# LVDS_eDP.net
KiCad netlist of a schematic drawn in Altium Designer
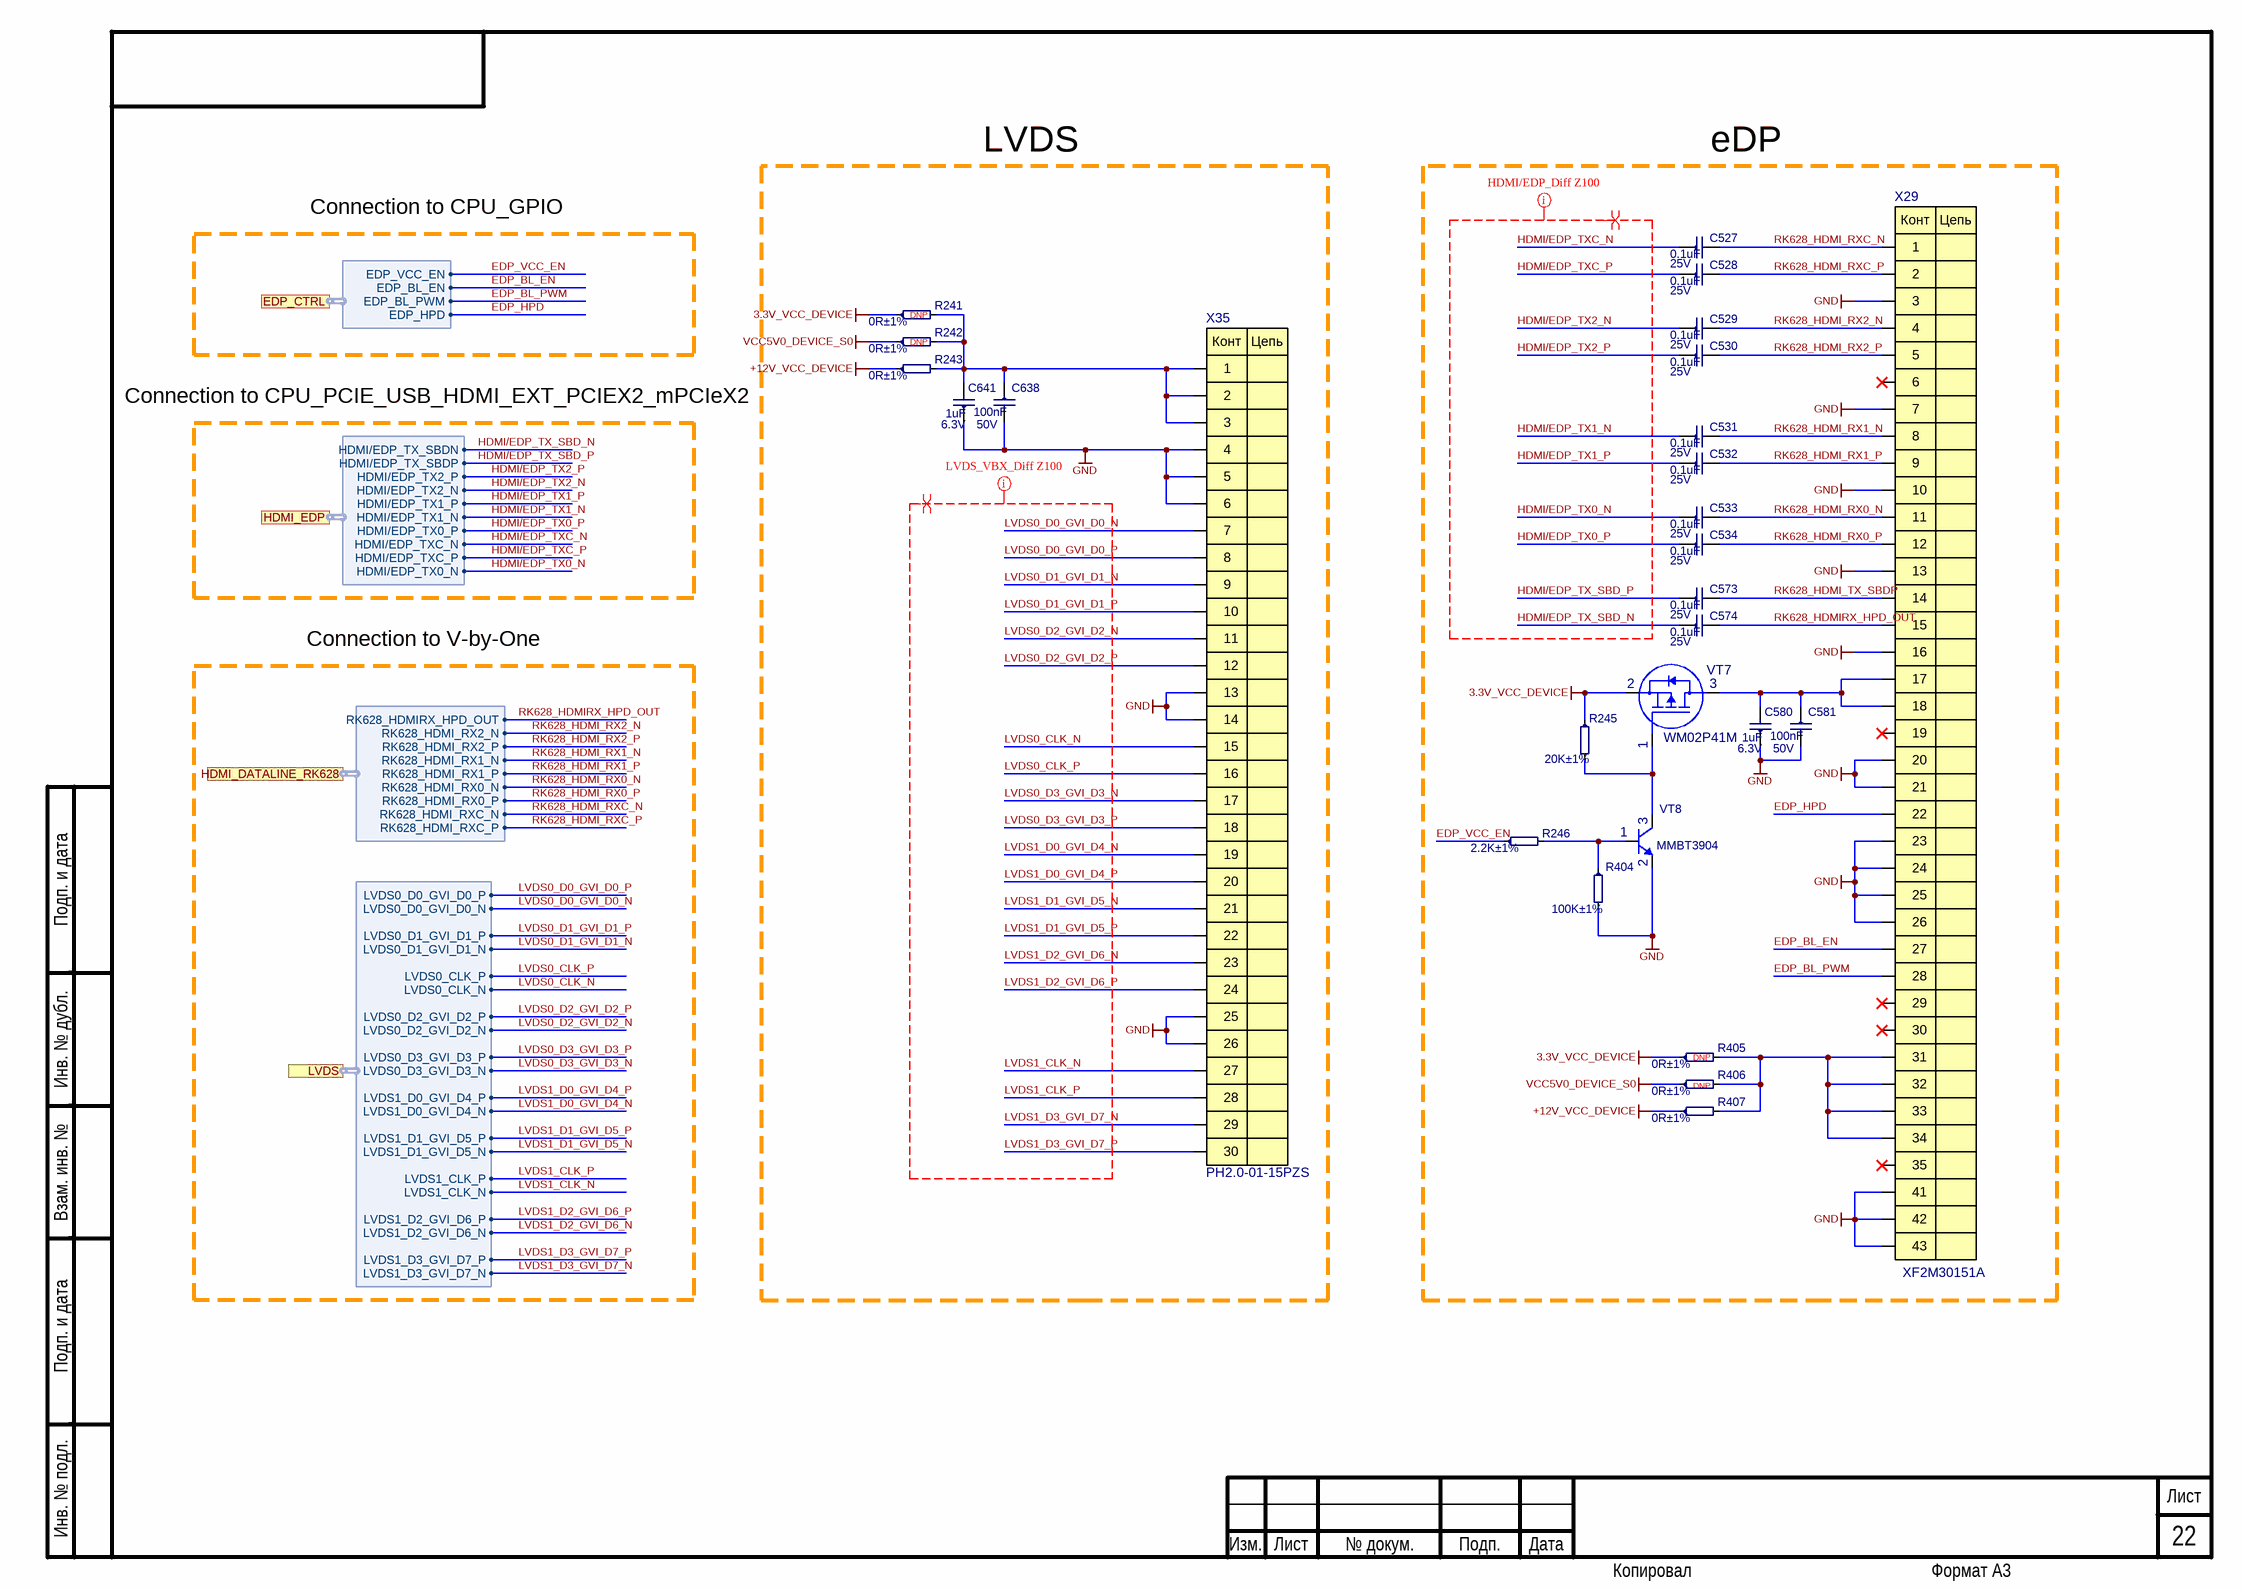
[diagram p0: LVDS_eDP.SchDoc]

(export (version "E")
  (design (tool "Eeschema 10.0.6"))
  (components
    (comp (ref "C527")
      (value "0.1uF")
      (footprint "C0201")
      (fields
        (field (name "VOLTAGE") "25V")
        (field (name "PART NUMBER") "0201-X5R-25V-0.1uF±10%")
        (field (name "TOLERANCE") "10%")
        (field (name "MANUFACTURER") "Yageo")
      )
      (libsource (lib "ATB") (part "C"))
    )
    (comp (ref "C528")
      (value "0.1uF")
      (footprint "C0201")
      (fields
        (field (name "VOLTAGE") "25V")
        (field (name "PART NUMBER") "0201-X5R-25V-0.1uF±10%")
        (field (name "TOLERANCE") "10%")
        (field (name "MANUFACTURER") "Yageo")
      )
      (libsource (lib "ATB") (part "C"))
    )
    (comp (ref "C529")
      (value "0.1uF")
      (footprint "C0201")
      (fields
        (field (name "VOLTAGE") "25V")
        (field (name "PART NUMBER") "0201-X5R-25V-0.1uF±10%")
        (field (name "TOLERANCE") "10%")
        (field (name "MANUFACTURER") "Yageo")
      )
      (libsource (lib "ATB") (part "C"))
    )
    (comp (ref "C530")
      (value "0.1uF")
      (footprint "C0201")
      (fields
        (field (name "VOLTAGE") "25V")
        (field (name "PART NUMBER") "0201-X5R-25V-0.1uF±10%")
        (field (name "TOLERANCE") "10%")
        (field (name "MANUFACTURER") "Yageo")
      )
      (libsource (lib "ATB") (part "C"))
    )
    (comp (ref "C531")
      (value "0.1uF")
      (footprint "C0201")
      (fields
        (field (name "VOLTAGE") "25V")
        (field (name "PART NUMBER") "0201-X5R-25V-0.1uF±10%")
        (field (name "TOLERANCE") "10%")
        (field (name "MANUFACTURER") "Yageo")
      )
      (libsource (lib "ATB") (part "C"))
    )
    (comp (ref "C532")
      (value "0.1uF")
      (footprint "C0201")
      (fields
        (field (name "VOLTAGE") "25V")
        (field (name "PART NUMBER") "0201-X5R-25V-0.1uF±10%")
        (field (name "TOLERANCE") "10%")
        (field (name "MANUFACTURER") "Yageo")
      )
      (libsource (lib "ATB") (part "C"))
    )
    (comp (ref "C533")
      (value "0.1uF")
      (footprint "C0201")
      (fields
        (field (name "VOLTAGE") "25V")
        (field (name "PART NUMBER") "0201-X5R-25V-0.1uF±10%")
        (field (name "TOLERANCE") "10%")
        (field (name "MANUFACTURER") "Yageo")
      )
      (libsource (lib "ATB") (part "C"))
    )
    (comp (ref "C534")
      (value "0.1uF")
      (footprint "C0201")
      (fields
        (field (name "VOLTAGE") "25V")
        (field (name "PART NUMBER") "0201-X5R-25V-0.1uF±10%")
        (field (name "TOLERANCE") "10%")
        (field (name "MANUFACTURER") "Yageo")
      )
      (libsource (lib "ATB") (part "C"))
    )
    (comp (ref "C573")
      (value "0.1uF")
      (footprint "C0201")
      (fields
        (field (name "VOLTAGE") "25V")
        (field (name "PART NUMBER") "0201-X5R-25V-0.1uF±10%")
        (field (name "TOLERANCE") "10%")
        (field (name "MANUFACTURER") "Yageo")
      )
      (libsource (lib "ATB") (part "C"))
    )
    (comp (ref "C574")
      (value "0.1uF")
      (footprint "C0201")
      (fields
        (field (name "VOLTAGE") "25V")
        (field (name "PART NUMBER") "0201-X5R-25V-0.1uF±10%")
        (field (name "TOLERANCE") "10%")
        (field (name "MANUFACTURER") "Yageo")
      )
      (libsource (lib "ATB") (part "C"))
    )
    (comp (ref "C580")
      (value "1uF")
      (footprint "C0201")
      (fields
        (field (name "VOLTAGE") "6.3V")
        (field (name "PART NUMBER") "0201-X5R-6.3V-1uF±20%")
        (field (name "TOLERANCE") "20%")
        (field (name "MANUFACTURER") "Murata Electronics")
      )
      (libsource (lib "ATB") (part "C"))
    )
    (comp (ref "C581")
      (value "100nF")
      (footprint "C0402")
      (description "Ceramic Capacitor 0402 100nF ±10% 50V X7R")
      (fields
        (field (name "VOLTAGE") "50V")
        (field (name "PART NUMBER") "0402-X7R-50V-0.1uF±10%")
        (field (name "TOLERANCE") "10%")
      )
      (libsource (lib "ATB") (part "C"))
    )
    (comp (ref "C638")
      (value "100nF")
      (footprint "C0402")
      (description "Ceramic Capacitor 0402 100nF ±10% 50V X7R")
      (fields
        (field (name "VOLTAGE") "50V")
        (field (name "PART NUMBER") "0402-X7R-50V-0.1uF±10%")
        (field (name "TOLERANCE") "10%")
      )
      (libsource (lib "ATB") (part "C"))
    )
    (comp (ref "C641")
      (value "1uF")
      (footprint "C0201")
      (fields
        (field (name "VOLTAGE") "6.3V")
        (field (name "PART NUMBER") "0201-X5R-6.3V-1uF±20%")
        (field (name "TOLERANCE") "20%")
        (field (name "MANUFACTURER") "Murata Electronics")
      )
      (libsource (lib "ATB") (part "C"))
    )
    (comp (ref "R241")
      (value "0R±1%")
      (footprint "R0402")
      (description "Chip Resistor 0402 0Ω ±1% 50V ±100ppm/℃ Thick Film")
      (fields (field (name "PART NUMBER") "0402-0.0625W-0R-100ppm±1%") (field (name "TOLERANCE") "1%"))
      (libsource (lib "ATB") (part "R"))
    )
    (comp (ref "R242")
      (value "0R±1%")
      (footprint "R0402")
      (description "Chip Resistor 0402 0Ω ±1% 50V ±100ppm/℃ Thick Film")
      (fields (field (name "PART NUMBER") "0402-0.0625W-0R-100ppm±1%") (field (name "TOLERANCE") "1%"))
      (libsource (lib "ATB") (part "R"))
    )
    (comp (ref "R243")
      (value "0R±1%")
      (footprint "R0402")
      (description "Chip Resistor 0402 0Ω ±1% 50V ±100ppm/℃ Thick Film")
      (fields (field (name "PART NUMBER") "0402-0.0625W-0R-100ppm±1%") (field (name "TOLERANCE") "1%"))
      (libsource (lib "ATB") (part "R"))
    )
    (comp (ref "R245")
      (value "20K±1%")
      (footprint "R0402")
      (description "Chip Resistor 0402 20kΩ ±1% 50V ±100ppm/℃ Thick Film")
      (fields (field (name "PART NUMBER") "0402-0.0625W-20K-100ppm±1%") (field (name "TOLERANCE") "1%"))
      (libsource (lib "ATB") (part "R"))
    )
    (comp (ref "R246")
      (value "2.2K±1%")
      (footprint "R0402")
      (fields
        (field (name "PART NUMBER") "0402-0.0625W-2.2K-100ppm±1%")
        (field (name "TOLERANCE") "1%")
        (field (name "MANUFACTURER") "Yageo")
      )
      (libsource (lib "ATB") (part "R"))
    )
    (comp (ref "R404")
      (value "100K±1%")
      (footprint "R0402")
      (description "Chip Resistor 0402 100kΩ ±1% 50V ±100ppm/℃ Thick Film")
      (fields (field (name "PART NUMBER") "0402-0.0625W-100K-100ppm±1%") (field (name "TOLERANCE") "1%"))
      (libsource (lib "ATB") (part "R"))
    )
    (comp (ref "R405")
      (value "0R±1%")
      (footprint "R0402")
      (description "Chip Resistor 0402 0Ω ±1% 50V ±100ppm/℃ Thick Film")
      (fields (field (name "PART NUMBER") "0402-0.0625W-0R-100ppm±1%") (field (name "TOLERANCE") "1%"))
      (libsource (lib "ATB") (part "R"))
    )
    (comp (ref "R406")
      (value "0R±1%")
      (footprint "R0402")
      (description "Chip Resistor 0402 0Ω ±1% 50V ±100ppm/℃ Thick Film")
      (fields (field (name "PART NUMBER") "0402-0.0625W-0R-100ppm±1%") (field (name "TOLERANCE") "1%"))
      (libsource (lib "ATB") (part "R"))
    )
    (comp (ref "R407")
      (value "0R±1%")
      (footprint "R0402")
      (description "Chip Resistor 0402 0Ω ±1% 50V ±100ppm/℃ Thick Film")
      (fields (field (name "PART NUMBER") "0402-0.0625W-0R-100ppm±1%") (field (name "TOLERANCE") "1%"))
      (libsource (lib "ATB") (part "R"))
    )
    (comp (ref "VT7")
      (value "WM02P41M")
      (footprint "SOT23")
      (description "Small signal mosfet")
      (fields (field (name "VOLTAGE") "-20V") (field (name "MANUFACTURER") "Wayon"))
      (libsource (lib "ATB") (part "WM02P41M"))
    )
    (comp (ref "VT8")
      (value "MMBT3904")
      (footprint "SOT23")
      (description "NPN transistor")
      (fields (field (name "VOLTAGE") "40V") (field (name "MANUFACTURER") "Diotec Semiconductor"))
      (libsource (lib "ATB") (part "BC846BLT1G"))
    )
    (comp (ref "X29")
      (value "XF2M30151A")
      (footprint "XF2M30151A")
      (description "FFC разъем, 30PIN, 0.5мм, 50В")
      (fields (field (name "MANUFACTURER") "Omron"))
      (libsource (lib "LIB_RK") (part "XF2M30151A"))
    )
    (comp (ref "X35")
      (value "PH2.0-01-15PZS")
      (footprint "PH2.0-01-15PZS")
      (description "Pin Header 30 Position 2mm Pitch Dual Row Through Hole -40℃~+105℃")
      (fields (field (name "MANUFACTURER") "XUNPU"))
      (libsource (lib "LIB_RK") (part "PH2.0-01-15PZS"))
    )
  )
  (nets
    (net (code "5") (name "+12V_VCC_DEVICE") (class "Default")
      (node (ref "R243") (pin "1") (pinfunction "1_1") (pintype "passive"))
      (node (ref "R407") (pin "1") (pinfunction "1_1") (pintype "passive"))
    )
    (net (code "6") (name "/EDP_BL_EN") (class "Default")
      (node (ref "X29") (pin "27") (pinfunction "27_27") (pintype "passive"))
    )
    (net (code "7") (name "/EDP_BL_PWM") (class "Default")
      (node (ref "X29") (pin "28") (pinfunction "28_28") (pintype "passive"))
    )
    (net (code "8") (name "/EDP_HPD") (class "Default")
      (node (ref "X29") (pin "22") (pinfunction "22_22") (pintype "passive"))
    )
    (net (code "9") (name "/EDP_VCC_EN") (class "Default")
      (node (ref "R246") (pin "1") (pinfunction "1_1") (pintype "passive"))
    )
    (net (code "10") (name "/HDMI{slash}EDP_TX0_N") (class "Default")
      (node (ref "C533") (pin "1") (pinfunction "1_1") (pintype "passive"))
    )
    (net (code "11") (name "/HDMI{slash}EDP_TX0_P") (class "Default")
      (node (ref "C534") (pin "1") (pinfunction "1_1") (pintype "passive"))
    )
    (net (code "12") (name "/HDMI{slash}EDP_TX1_N") (class "Default")
      (node (ref "C531") (pin "1") (pinfunction "1_1") (pintype "passive"))
    )
    (net (code "13") (name "/HDMI{slash}EDP_TX1_P") (class "Default")
      (node (ref "C532") (pin "1") (pinfunction "1_1") (pintype "passive"))
    )
    (net (code "14") (name "/HDMI{slash}EDP_TX2_N") (class "Default")
      (node (ref "C529") (pin "1") (pinfunction "1_1") (pintype "passive"))
    )
    (net (code "15") (name "/HDMI{slash}EDP_TX2_P") (class "Default")
      (node (ref "C530") (pin "1") (pinfunction "1_1") (pintype "passive"))
    )
    (net (code "16") (name "/HDMI{slash}EDP_TXC_N") (class "Default")
      (node (ref "C527") (pin "1") (pinfunction "1_1") (pintype "passive"))
    )
    (net (code "17") (name "/HDMI{slash}EDP_TXC_P") (class "Default")
      (node (ref "C528") (pin "1") (pinfunction "1_1") (pintype "passive"))
    )
    (net (code "18") (name "/HDMI{slash}EDP_TX_SBD_N") (class "Default")
      (node (ref "C574") (pin "1") (pinfunction "1_1") (pintype "passive"))
    )
    (net (code "19") (name "/HDMI{slash}EDP_TX_SBD_P") (class "Default")
      (node (ref "C573") (pin "1") (pinfunction "1_1") (pintype "passive"))
    )
    (net (code "20") (name "/LVDS0_CLK_N") (class "Default")
      (node (ref "X35") (pin "15") (pinfunction "15_15") (pintype "passive"))
    )
    (net (code "21") (name "/LVDS0_CLK_P") (class "Default")
      (node (ref "X35") (pin "16") (pinfunction "16_16") (pintype "passive"))
    )
    (net (code "22") (name "/LVDS0_D0_GVI_D0_N") (class "Default")
      (node (ref "X35") (pin "7") (pinfunction "7_7") (pintype "passive"))
    )
    (net (code "23") (name "/LVDS0_D0_GVI_D0_P") (class "Default")
      (node (ref "X35") (pin "8") (pinfunction "8_8") (pintype "passive"))
    )
    (net (code "24") (name "/LVDS0_D1_GVI_D1_N") (class "Default")
      (node (ref "X35") (pin "9") (pinfunction "9_9") (pintype "passive"))
    )
    (net (code "25") (name "/LVDS0_D1_GVI_D1_P") (class "Default")
      (node (ref "X35") (pin "10") (pinfunction "10_10") (pintype "passive"))
    )
    (net (code "26") (name "/LVDS0_D2_GVI_D2_N") (class "Default")
      (node (ref "X35") (pin "11") (pinfunction "11_11") (pintype "passive"))
    )
    (net (code "27") (name "/LVDS0_D2_GVI_D2_P") (class "Default")
      (node (ref "X35") (pin "12") (pinfunction "12_12") (pintype "passive"))
    )
    (net (code "28") (name "/LVDS0_D3_GVI_D3_N") (class "Default")
      (node (ref "X35") (pin "17") (pinfunction "17_17") (pintype "passive"))
    )
    (net (code "29") (name "/LVDS0_D3_GVI_D3_P") (class "Default")
      (node (ref "X35") (pin "18") (pinfunction "18_18") (pintype "passive"))
    )
    (net (code "30") (name "/LVDS1_CLK_N") (class "Default")
      (node (ref "X35") (pin "27") (pinfunction "27_27") (pintype "passive"))
    )
    (net (code "31") (name "/LVDS1_CLK_P") (class "Default")
      (node (ref "X35") (pin "28") (pinfunction "28_28") (pintype "passive"))
    )
    (net (code "32") (name "/LVDS1_D0_GVI_D4_N") (class "Default")
      (node (ref "X35") (pin "19") (pinfunction "19_19") (pintype "passive"))
    )
    (net (code "33") (name "/LVDS1_D0_GVI_D4_P") (class "Default")
      (node (ref "X35") (pin "20") (pinfunction "20_20") (pintype "passive"))
    )
    (net (code "34") (name "/LVDS1_D1_GVI_D5_N") (class "Default")
      (node (ref "X35") (pin "21") (pinfunction "21_21") (pintype "passive"))
    )
    (net (code "35") (name "/LVDS1_D1_GVI_D5_P") (class "Default")
      (node (ref "X35") (pin "22") (pinfunction "22_22") (pintype "passive"))
    )
    (net (code "36") (name "/LVDS1_D2_GVI_D6_N") (class "Default")
      (node (ref "X35") (pin "23") (pinfunction "23_23") (pintype "passive"))
    )
    (net (code "37") (name "/LVDS1_D2_GVI_D6_P") (class "Default")
      (node (ref "X35") (pin "24") (pinfunction "24_24") (pintype "passive"))
    )
    (net (code "38") (name "/LVDS1_D3_GVI_D7_N") (class "Default")
      (node (ref "X35") (pin "29") (pinfunction "29_29") (pintype "passive"))
    )
    (net (code "39") (name "/LVDS1_D3_GVI_D7_P") (class "Default")
      (node (ref "X35") (pin "30") (pinfunction "30_30") (pintype "passive"))
    )
    (net (code "40") (name "/RK628_HDMIRX_HPD_OUT") (class "Default")
      (node (ref "C574") (pin "2") (pinfunction "2_2") (pintype "passive"))
      (node (ref "X29") (pin "15") (pinfunction "15_15") (pintype "passive"))
    )
    (net (code "41") (name "/RK628_HDMI_RX0_N") (class "Default")
      (node (ref "C533") (pin "2") (pinfunction "2_2") (pintype "passive"))
      (node (ref "X29") (pin "11") (pinfunction "11_11") (pintype "passive"))
    )
    (net (code "42") (name "/RK628_HDMI_RX0_P") (class "Default")
      (node (ref "C534") (pin "2") (pinfunction "2_2") (pintype "passive"))
      (node (ref "X29") (pin "12") (pinfunction "12_12") (pintype "passive"))
    )
    (net (code "43") (name "/RK628_HDMI_RX1_N") (class "Default")
      (node (ref "C531") (pin "2") (pinfunction "2_2") (pintype "passive"))
      (node (ref "X29") (pin "8") (pinfunction "8_8") (pintype "passive"))
    )
    (net (code "44") (name "/RK628_HDMI_RX1_P") (class "Default")
      (node (ref "C532") (pin "2") (pinfunction "2_2") (pintype "passive"))
      (node (ref "X29") (pin "9") (pinfunction "9_9") (pintype "passive"))
    )
    (net (code "45") (name "/RK628_HDMI_RX2_N") (class "Default")
      (node (ref "C529") (pin "2") (pinfunction "2_2") (pintype "passive"))
      (node (ref "X29") (pin "4") (pinfunction "4_4") (pintype "passive"))
    )
    (net (code "46") (name "/RK628_HDMI_RX2_P") (class "Default")
      (node (ref "C530") (pin "2") (pinfunction "2_2") (pintype "passive"))
      (node (ref "X29") (pin "5") (pinfunction "5_5") (pintype "passive"))
    )
    (net (code "47") (name "/RK628_HDMI_RXC_N") (class "Default")
      (node (ref "C527") (pin "2") (pinfunction "2_2") (pintype "passive"))
      (node (ref "X29") (pin "1") (pinfunction "1_1") (pintype "passive"))
    )
    (net (code "48") (name "/RK628_HDMI_RXC_P") (class "Default")
      (node (ref "C528") (pin "2") (pinfunction "2_2") (pintype "passive"))
      (node (ref "X29") (pin "2") (pinfunction "2_2") (pintype "passive"))
    )
    (net (code "49") (name "/RK628_HDMI_TX_SBDP") (class "Default")
      (node (ref "C573") (pin "2") (pinfunction "2_2") (pintype "passive"))
      (node (ref "X29") (pin "14") (pinfunction "14_14") (pintype "passive"))
    )
    (net (code "54") (name "3.3V_VCC_DEVICE") (class "Default")
      (node (ref "R241") (pin "1") (pinfunction "1_1") (pintype "passive"))
      (node (ref "R245") (pin "1") (pinfunction "1_1") (pintype "passive"))
      (node (ref "R405") (pin "1") (pinfunction "1_1") (pintype "passive"))
      (node (ref "VT7") (pin "2") (pinfunction "2_2") (pintype "passive"))
    )
    (net (code "55") (name "GND") (class "Default")
      (node (ref "C580") (pin "1") (pinfunction "1_1") (pintype "passive"))
      (node (ref "C581") (pin "2") (pinfunction "2_2") (pintype "passive"))
      (node (ref "C638") (pin "2") (pinfunction "2_2") (pintype "passive"))
      (node (ref "C641") (pin "1") (pinfunction "1_1") (pintype "passive"))
      (node (ref "R404") (pin "2") (pinfunction "2_2") (pintype "passive"))
      (node (ref "VT8") (pin "2") (pinfunction "E_2") (pintype "passive"))
      (node (ref "X29") (pin "10") (pinfunction "10_10") (pintype "passive"))
      (node (ref "X29") (pin "13") (pinfunction "13_13") (pintype "passive"))
      (node (ref "X29") (pin "16") (pinfunction "16_16") (pintype "passive"))
      (node (ref "X29") (pin "20") (pinfunction "20_20") (pintype "passive"))
      (node (ref "X29") (pin "21") (pinfunction "21_21") (pintype "passive"))
      (node (ref "X29") (pin "23") (pinfunction "23_23") (pintype "passive"))
      (node (ref "X29") (pin "24") (pinfunction "24_24") (pintype "passive"))
      (node (ref "X29") (pin "25") (pinfunction "25_25") (pintype "passive"))
      (node (ref "X29") (pin "26") (pinfunction "26_26") (pintype "passive"))
      (node (ref "X29") (pin "3") (pinfunction "3_3") (pintype "passive"))
      (node (ref "X29") (pin "41") (pinfunction "41_41") (pintype "passive"))
      (node (ref "X29") (pin "42") (pinfunction "42_42") (pintype "passive"))
      (node (ref "X29") (pin "43") (pinfunction "43_43") (pintype "passive"))
      (node (ref "X29") (pin "7") (pinfunction "7_7") (pintype "passive"))
      (node (ref "X35") (pin "13") (pinfunction "13_13") (pintype "passive"))
      (node (ref "X35") (pin "14") (pinfunction "14_14") (pintype "passive"))
      (node (ref "X35") (pin "25") (pinfunction "25_25") (pintype "passive"))
      (node (ref "X35") (pin "26") (pinfunction "26_26") (pintype "passive"))
      (node (ref "X35") (pin "4") (pinfunction "4_4") (pintype "passive"))
      (node (ref "X35") (pin "5") (pinfunction "5_5") (pintype "passive"))
      (node (ref "X35") (pin "6") (pinfunction "6_6") (pintype "passive"))
    )
    (net (code "56") (name "Net-(C580-Pad2)") (class "Default")
      (node (ref "C580") (pin "2") (pinfunction "2_2") (pintype "passive"))
      (node (ref "C581") (pin "1") (pinfunction "1_1") (pintype "passive"))
      (node (ref "VT7") (pin "3") (pinfunction "3_3") (pintype "passive"))
      (node (ref "X29") (pin "17") (pinfunction "17_17") (pintype "passive"))
      (node (ref "X29") (pin "18") (pinfunction "18_18") (pintype "passive"))
    )
    (net (code "57") (name "Net-(C638-Pad1)") (class "Default")
      (node (ref "C638") (pin "1") (pinfunction "1_1") (pintype "passive"))
      (node (ref "C641") (pin "2") (pinfunction "2_2") (pintype "passive"))
      (node (ref "R241") (pin "2") (pinfunction "2_2") (pintype "passive"))
      (node (ref "R242") (pin "2") (pinfunction "2_2") (pintype "passive"))
      (node (ref "R243") (pin "2") (pinfunction "2_2") (pintype "passive"))
      (node (ref "X35") (pin "1") (pinfunction "1_1") (pintype "passive"))
      (node (ref "X35") (pin "2") (pinfunction "2_2") (pintype "passive"))
      (node (ref "X35") (pin "3") (pinfunction "3_3") (pintype "passive"))
    )
    (net (code "58") (name "Net-(R405-Pad2)") (class "Default")
      (node (ref "R405") (pin "2") (pinfunction "2_2") (pintype "passive"))
      (node (ref "R406") (pin "2") (pinfunction "2_2") (pintype "passive"))
      (node (ref "R407") (pin "2") (pinfunction "2_2") (pintype "passive"))
      (node (ref "X29") (pin "31") (pinfunction "31_31") (pintype "passive"))
      (node (ref "X29") (pin "32") (pinfunction "32_32") (pintype "passive"))
      (node (ref "X29") (pin "33") (pinfunction "33_33") (pintype "passive"))
      (node (ref "X29") (pin "34") (pinfunction "34_34") (pintype "passive"))
    )
    (net (code "59") (name "Net-(VT8-B)") (class "Default")
      (node (ref "R246") (pin "2") (pinfunction "2_2") (pintype "passive"))
      (node (ref "R404") (pin "1") (pinfunction "1_1") (pintype "passive"))
      (node (ref "VT8") (pin "1") (pinfunction "B_1") (pintype "passive"))
    )
    (net (code "60") (name "Net-(VT8-C)") (class "Default")
      (node (ref "R245") (pin "2") (pinfunction "2_2") (pintype "passive"))
      (node (ref "VT7") (pin "1") (pinfunction "1_1") (pintype "passive"))
      (node (ref "VT8") (pin "3") (pinfunction "C_3") (pintype "passive"))
    )
    (net (code "61") (name "VCC5V0_DEVICE_S0") (class "Default")
      (node (ref "R242") (pin "1") (pinfunction "1_1") (pintype "passive"))
      (node (ref "R406") (pin "1") (pinfunction "1_1") (pintype "passive"))
    )
    (net (code "62") (name "unconnected-(X29-Pad6)") (class "Default")
      (node (ref "X29") (pin "6") (pinfunction "6_6") (pintype "passive+no_connect"))
    )
    (net (code "63") (name "unconnected-(X29-Pad19)") (class "Default")
      (node (ref "X29") (pin "19") (pinfunction "19_19") (pintype "passive+no_connect"))
    )
    (net (code "64") (name "unconnected-(X29-Pad29)") (class "Default")
      (node (ref "X29") (pin "29") (pinfunction "29_29") (pintype "passive+no_connect"))
    )
    (net (code "65") (name "unconnected-(X29-Pad30)") (class "Default")
      (node (ref "X29") (pin "30") (pinfunction "30_30") (pintype "passive+no_connect"))
    )
    (net (code "66") (name "unconnected-(X29-Pad35)") (class "Default")
      (node (ref "X29") (pin "35") (pinfunction "35_35") (pintype "passive+no_connect"))
    )
  )
)
